# MCU.net
KiCad netlist of a schematic drawn in Altium Designer
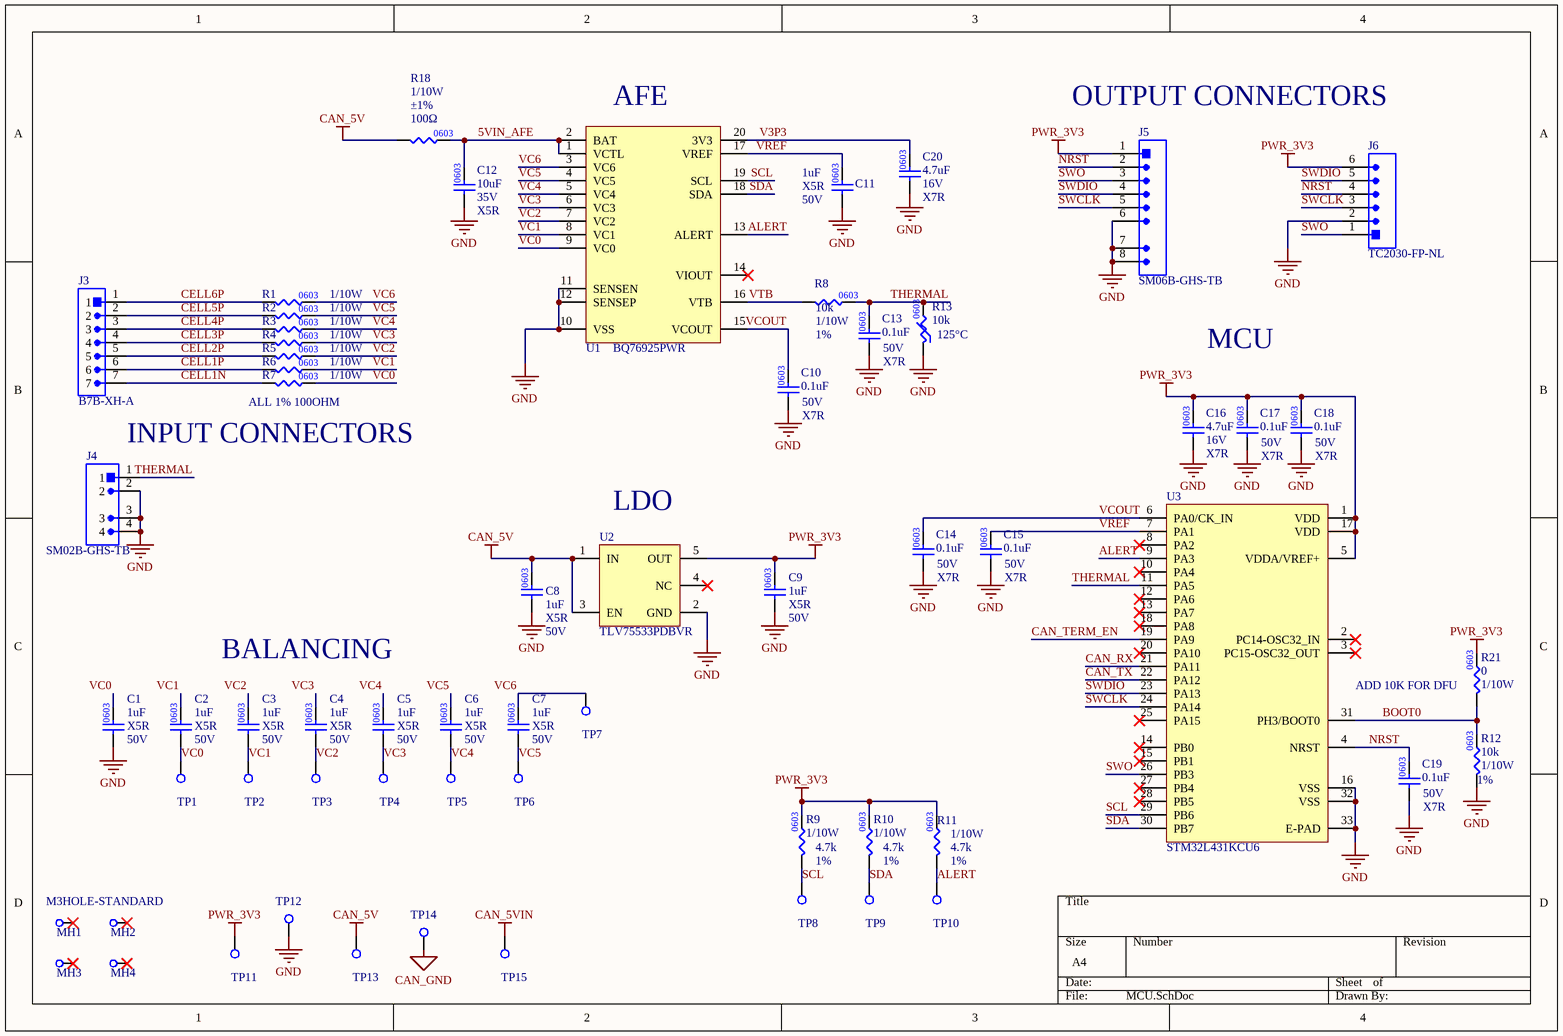
[diagram p0: MCU.SchDoc]

(export (version "E")
  (design (tool "Eeschema 10.0.6"))
  (components
    (comp (ref "C1")
      (value "GRT188R61H105KE13D")
      (footprint ".CAP_0603-Footprint-1")
      (description "CAP CER 1UF 50V X5R 0603")
      (fields
        (field (name "DIELECTRIC") "X5R")
        (field (name "VOLTAGE") "50V")
        (field (name "CAPACITANCE") "1uF")
      )
      (libsource (lib "WARG") (part "CAP"))
    )
    (comp (ref "C2")
      (value "GRT188R61H105KE13D")
      (footprint ".CAP_0603-Footprint-1")
      (description "CAP CER 1UF 50V X5R 0603")
      (fields
        (field (name "DIELECTRIC") "X5R")
        (field (name "VOLTAGE") "50V")
        (field (name "CAPACITANCE") "1uF")
      )
      (libsource (lib "WARG") (part "CAP"))
    )
    (comp (ref "C3")
      (value "GRT188R61H105KE13D")
      (footprint ".CAP_0603-Footprint-1")
      (description "CAP CER 1UF 50V X5R 0603")
      (fields
        (field (name "DIELECTRIC") "X5R")
        (field (name "VOLTAGE") "50V")
        (field (name "CAPACITANCE") "1uF")
      )
      (libsource (lib "WARG") (part "CAP"))
    )
    (comp (ref "C4")
      (value "GRT188R61H105KE13D")
      (footprint ".CAP_0603-Footprint-1")
      (description "CAP CER 1UF 50V X5R 0603")
      (fields
        (field (name "DIELECTRIC") "X5R")
        (field (name "VOLTAGE") "50V")
        (field (name "CAPACITANCE") "1uF")
      )
      (libsource (lib "WARG") (part "CAP"))
    )
    (comp (ref "C5")
      (value "GRT188R61H105KE13D")
      (footprint ".CAP_0603-Footprint-1")
      (description "CAP CER 1UF 50V X5R 0603")
      (fields
        (field (name "DIELECTRIC") "X5R")
        (field (name "VOLTAGE") "50V")
        (field (name "CAPACITANCE") "1uF")
      )
      (libsource (lib "WARG") (part "CAP"))
    )
    (comp (ref "C6")
      (value "GRT188R61H105KE13D")
      (footprint ".CAP_0603-Footprint-1")
      (description "CAP CER 1UF 50V X5R 0603")
      (fields
        (field (name "DIELECTRIC") "X5R")
        (field (name "VOLTAGE") "50V")
        (field (name "CAPACITANCE") "1uF")
      )
      (libsource (lib "WARG") (part "CAP"))
    )
    (comp (ref "C7")
      (value "GRT188R61H105KE13D")
      (footprint ".CAP_0603-Footprint-1")
      (description "CAP CER 1UF 50V X5R 0603")
      (fields
        (field (name "DIELECTRIC") "X5R")
        (field (name "VOLTAGE") "50V")
        (field (name "CAPACITANCE") "1uF")
      )
      (libsource (lib "WARG") (part "CAP"))
    )
    (comp (ref "C8")
      (value "GRT188R61H105KE13D")
      (footprint ".CAP_0603-Footprint-1")
      (description "CAP CER 1UF 50V X5R 0603")
      (fields
        (field (name "DIELECTRIC") "X5R")
        (field (name "VOLTAGE") "50V")
        (field (name "CAPACITANCE") "1uF")
      )
      (libsource (lib "WARG") (part "CAP"))
    )
    (comp (ref "C9")
      (value "GRT188R61H105KE13D")
      (footprint ".CAP_0603-Footprint-1")
      (description "CAP CER 1UF 50V X5R 0603")
      (fields
        (field (name "DIELECTRIC") "X5R")
        (field (name "VOLTAGE") "50V")
        (field (name "CAPACITANCE") "1uF")
      )
      (libsource (lib "WARG") (part "CAP"))
    )
    (comp (ref "C10")
      (value "0.1uF")
      (footprint ".CAP_0603-Footprint-1")
      (description "CAP CER 0.1uF 50V X7R 0603")
      (fields
        (field (name "DIELECTRIC") "X7R")
        (field (name "VOLTAGE") "50V")
        (field (name "TOLERANCE") "10%")
        (field (name "Comment") "GCM188R71H104KA57D")
      )
      (libsource (lib "WARG") (part ".CAP_0603-Symbol-1"))
    )
    (comp (ref "C11")
      (value "GRT188R61H105KE13D")
      (footprint ".CAP_0603-Footprint-1")
      (description "CAP CER 1UF 50V X5R 0603")
      (fields
        (field (name "DIELECTRIC") "X5R")
        (field (name "VOLTAGE") "50V")
        (field (name "CAPACITANCE") "1uF")
      )
      (libsource (lib "WARG") (part "CAP"))
    )
    (comp (ref "C12")
      (value "GRM188R6YA106MA73D")
      (footprint ".CAP_0603-Footprint-1")
      (description "CAP CER 10UF 35V X5R 0603")
      (fields
        (field (name "TOLERANCE") "±20%")
        (field (name "CAPACITANCE") "10uF")
        (field (name "VOLTAGE") "35V")
        (field (name "TEMPERATURE COEFFICIENT") "X5R")
      )
      (libsource (lib "WARG") (part ".CAP_0603-Symbol-1"))
    )
    (comp (ref "C13")
      (value "0.1uF")
      (footprint ".CAP_0603-Footprint-1")
      (description "CAP CER 0.1uF 50V X7R 0603")
      (fields
        (field (name "DIELECTRIC") "X7R")
        (field (name "VOLTAGE") "50V")
        (field (name "TOLERANCE") "10%")
        (field (name "Comment") "GCM188R71H104KA57D")
      )
      (libsource (lib "WARG") (part ".CAP_0603-Symbol-1"))
    )
    (comp (ref "C14")
      (value "0.1uF")
      (footprint ".CAP_0603-Footprint-1")
      (description "CAP CER 0.1uF 50V X7R 0603")
      (fields
        (field (name "DIELECTRIC") "X7R")
        (field (name "VOLTAGE") "50V")
        (field (name "TOLERANCE") "10%")
        (field (name "Comment") "GCM188R71H104KA57D")
      )
      (libsource (lib "WARG") (part ".CAP_0603-Symbol-1"))
    )
    (comp (ref "C15")
      (value "0.1uF")
      (footprint ".CAP_0603-Footprint-1")
      (description "CAP CER 0.1uF 50V X7R 0603")
      (fields
        (field (name "DIELECTRIC") "X7R")
        (field (name "VOLTAGE") "50V")
        (field (name "TOLERANCE") "10%")
        (field (name "Comment") "GCM188R71H104KA57D")
      )
      (libsource (lib "WARG") (part ".CAP_0603-Symbol-1"))
    )
    (comp (ref "C16")
      (value "4.7uF")
      (footprint ".CAP_0603-Footprint-1")
      (description "CAP CER 4.7UF 16V X7R 0603")
      (fields
        (field (name "VOLTAGE RATING") "16V")
        (field (name "TEMPERATURE COEFFICIENT") "X7R")
        (field (name "Comment") "GRM188Z71C475KE21J")
      )
      (libsource (lib "WARG") (part ".CAP_0603-Symbol-1"))
    )
    (comp (ref "C17")
      (value "0.1uF")
      (footprint ".CAP_0603-Footprint-1")
      (description "CAP CER 0.1uF 50V X7R 0603")
      (fields
        (field (name "DIELECTRIC") "X7R")
        (field (name "VOLTAGE") "50V")
        (field (name "TOLERANCE") "10%")
        (field (name "Comment") "GCM188R71H104KA57D")
      )
      (libsource (lib "WARG") (part ".CAP_0603-Symbol-1"))
    )
    (comp (ref "C18")
      (value "0.1uF")
      (footprint ".CAP_0603-Footprint-1")
      (description "CAP CER 0.1uF 50V X7R 0603")
      (fields
        (field (name "DIELECTRIC") "X7R")
        (field (name "VOLTAGE") "50V")
        (field (name "TOLERANCE") "10%")
        (field (name "Comment") "GCM188R71H104KA57D")
      )
      (libsource (lib "WARG") (part ".CAP_0603-Symbol-1"))
    )
    (comp (ref "C19")
      (value "0.1uF")
      (footprint ".CAP_0603-Footprint-1")
      (description "CAP CER 0.1uF 50V X7R 0603")
      (fields
        (field (name "DIELECTRIC") "X7R")
        (field (name "VOLTAGE") "50V")
        (field (name "TOLERANCE") "10%")
        (field (name "Comment") "GCM188R71H104KA57D")
      )
      (libsource (lib "WARG") (part ".CAP_0603-Symbol-1"))
    )
    (comp (ref "C20")
      (value "4.7uF")
      (footprint ".CAP_0603-Footprint-1")
      (description "CAP CER 4.7UF 16V X7R 0603")
      (fields
        (field (name "VOLTAGE RATING") "16V")
        (field (name "TEMPERATURE COEFFICIENT") "X7R")
        (field (name "Comment") "GRM188Z71C475KE21J")
      )
      (libsource (lib "WARG") (part ".CAP_0603-Symbol-1"))
    )
    (comp (ref "J3")
      (value "B7B-XH-A")
      (footprint "JST_B7B-XH-A")
      (description "Connector Header Through Hole 7 position 0.098 (2.50mm)")
      (fields (field (name "MF") "JST Sales"))
      (libsource (lib "WARG") (part "B7B-XH-A"))
    )
    (comp (ref "J4")
      (value "SM02B-GHS-TB")
      (footprint "SM02B-GHS-TB-Footprint-1")
      (description "CONN HEADER SMD R/A 2POS 1.25MM")
      (libsource (lib "WARG") (part "SM02B-GHS-TB-Symbol-1"))
    )
    (comp (ref "J5")
      (value "SM06B-GHS-TB")
      (footprint "SM06B-GHS-TB")
      (description "CONN HEADER SMD R/A 6POS 1.25MM")
      (fields (field (name "VOLTAGE") "50V"))
      (libsource (lib "WARG") (part "SM06B-GHS-TB(LF)(SN)-Symbol-1"))
    )
    (comp (ref "J6")
      (value "TC2030-FP-NL")
      (footprint "TC2030-FP-NL")
      (description "For TC2030-CTX-NL-STDC14 for use with STM32 processors with STLINK-V3 /STLINK-V3MINI")
      (fields (field (name "MANUFACTURER") "Tag-Connect"))
      (libsource (lib "WARG") (part "TC2030-FP-NL"))
    )
    (comp (ref "MH1")
      (value "M3HOLE-STANDARD")
      (footprint "M3HOLE-STANDARD-Footprint-1")
      (description "Standard M3 Mounting hole as defined by mech team, see confluence for reasonning")
      (libsource (lib "WARG") (part "M2HOLE-STANDARD-Symbol-1"))
    )
    (comp (ref "MH2")
      (value "M3HOLE-STANDARD")
      (footprint "M3HOLE-STANDARD-Footprint-1")
      (description "Standard M3 Mounting hole as defined by mech team, see confluence for reasonning")
      (libsource (lib "WARG") (part "M2HOLE-STANDARD-Symbol-1"))
    )
    (comp (ref "MH3")
      (value "M3HOLE-STANDARD")
      (footprint "M3HOLE-STANDARD-Footprint-1")
      (description "Standard M3 Mounting hole as defined by mech team, see confluence for reasonning")
      (libsource (lib "WARG") (part "M2HOLE-STANDARD-Symbol-1"))
    )
    (comp (ref "MH4")
      (value "M3HOLE-STANDARD")
      (footprint "M3HOLE-STANDARD-Footprint-1")
      (description "Standard M3 Mounting hole as defined by mech team, see confluence for reasonning")
      (libsource (lib "WARG") (part "M2HOLE-STANDARD-Symbol-1"))
    )
    (comp (ref "R1")
      (value "RC0603FR-07100RL")
      (footprint ".RES_0603-Footprint-1")
      (description "RES 100 OHM 1% 1/10W 0603")
      (fields (field (name "TOLERANCE") "±1%") (field (name "POWER") "1/10W"))
      (libsource (lib "WARG") (part ".RES_0603-Symbol-1"))
    )
    (comp (ref "R2")
      (value "RC0603FR-07100RL")
      (footprint ".RES_0603-Footprint-1")
      (description "RES 100 OHM 1% 1/10W 0603")
      (fields (field (name "TOLERANCE") "±1%") (field (name "POWER") "1/10W"))
      (libsource (lib "WARG") (part ".RES_0603-Symbol-1"))
    )
    (comp (ref "R3")
      (value "RC0603FR-07100RL")
      (footprint ".RES_0603-Footprint-1")
      (description "RES 100 OHM 1% 1/10W 0603")
      (fields (field (name "TOLERANCE") "±1%") (field (name "POWER") "1/10W"))
      (libsource (lib "WARG") (part ".RES_0603-Symbol-1"))
    )
    (comp (ref "R4")
      (value "RC0603FR-07100RL")
      (footprint ".RES_0603-Footprint-1")
      (description "RES 100 OHM 1% 1/10W 0603")
      (fields (field (name "TOLERANCE") "±1%") (field (name "POWER") "1/10W"))
      (libsource (lib "WARG") (part ".RES_0603-Symbol-1"))
    )
    (comp (ref "R5")
      (value "RC0603FR-07100RL")
      (footprint ".RES_0603-Footprint-1")
      (description "RES 100 OHM 1% 1/10W 0603")
      (fields (field (name "TOLERANCE") "±1%") (field (name "POWER") "1/10W"))
      (libsource (lib "WARG") (part ".RES_0603-Symbol-1"))
    )
    (comp (ref "R6")
      (value "RC0603FR-07100RL")
      (footprint ".RES_0603-Footprint-1")
      (description "RES 100 OHM 1% 1/10W 0603")
      (fields (field (name "TOLERANCE") "±1%") (field (name "POWER") "1/10W"))
      (libsource (lib "WARG") (part ".RES_0603-Symbol-1"))
    )
    (comp (ref "R7")
      (value "RC0603FR-07100RL")
      (footprint ".RES_0603-Footprint-1")
      (description "RES 100 OHM 1% 1/10W 0603")
      (fields (field (name "TOLERANCE") "±1%") (field (name "POWER") "1/10W"))
      (libsource (lib "WARG") (part ".RES_0603-Symbol-1"))
    )
    (comp (ref "R8")
      (value "10k")
      (footprint ".RES_0603-Footprint-1")
      (description "RES 10K OHM 1% 1/10W 0603")
      (fields
        (field (name "TOLERANCE") "1%")
        (field (name "POWER") "1/10W")
        (field (name "Comment") "RC0603FR-0710KL")
      )
      (libsource (lib "WARG") (part ".RES_0603-Symbol-1"))
    )
    (comp (ref "R9")
      (value "RC0603FR-074K7L")
      (footprint ".RES_0603-Footprint-1")
      (description "RES 4.7K OHM 1% 1/10W 0603")
      (fields
        (field (name "TOLERANCE") "1%")
        (field (name "POWER") "1/10W")
        (field (name "RESISTANCE") "4.7k")
      )
      (libsource (lib "WARG") (part ".RES_0603-Symbol-1"))
    )
    (comp (ref "R10")
      (value "RC0603FR-074K7L")
      (footprint ".RES_0603-Footprint-1")
      (description "RES 4.7K OHM 1% 1/10W 0603")
      (fields
        (field (name "TOLERANCE") "1%")
        (field (name "POWER") "1/10W")
        (field (name "RESISTANCE") "4.7k")
      )
      (libsource (lib "WARG") (part ".RES_0603-Symbol-1"))
    )
    (comp (ref "R11")
      (value "RC0603FR-074K7L")
      (footprint ".RES_0603-Footprint-1")
      (description "RES 4.7K OHM 1% 1/10W 0603")
      (fields
        (field (name "TOLERANCE") "1%")
        (field (name "POWER") "1/10W")
        (field (name "RESISTANCE") "4.7k")
      )
      (libsource (lib "WARG") (part ".RES_0603-Symbol-1"))
    )
    (comp (ref "R12")
      (value "10k")
      (footprint ".RES_0603-Footprint-1")
      (description "RES 10K OHM 1% 1/10W 0603")
      (fields
        (field (name "TOLERANCE") "1%")
        (field (name "POWER") "1/10W")
        (field (name "Comment") "RC0603FR-0710KL")
      )
      (libsource (lib "WARG") (part ".RES_0603-Symbol-1"))
    )
    (comp (ref "R13")
      (value "10k")
      (footprint ".RES_0603-Footprint-1")
      (description "THERMISTOR NTC 10KOHM 3380K 0603")
      (fields
        (field (name "TOLERANCE") "1%")
        (field (name "MAX OPERATING TEMPERATURE") "125°C")
        (field (name "Comment") "NTCG163JF103FT1")
      )
      (libsource (lib "WARG") (part ".THERMISTOR_0603-Symbol-1"))
    )
    (comp (ref "R18")
      (value "RC0603FR-07100RL")
      (footprint ".RES_0603-Footprint-1")
      (description "RES 100 OHM 1% 1/10W 0603")
      (fields
        (field (name "RESISTANCE") "100Ω")
        (field (name "TOLERANCE") "±1%")
        (field (name "POWER") "1/10W")
      )
      (libsource (lib "WARG") (part ".RES_0603-Symbol-1"))
    )
    (comp (ref "R21")
      (value "0")
      (footprint ".RES_0603-Footprint-1")
      (description "RES 0 OHM 1% 1/10W 0603")
      (fields
        (field (name "POWER") "1/10W")
        (field (name "TOLERANCE") "1%")
        (field (name "Comment") "RC0603JR-070RL")
      )
      (libsource (lib "WARG") (part ".RES_0603-Symbol-1"))
    )
    (comp (ref "TP1")
      (value "TESTINGPOINT_1MM")
      (footprint "TESTINGPOINT_1MM-Footprint-1")
      (description "Testing Point 1mm Radius")
      (libsource (lib "WARG") (part "TESTINGPOINT_1MM-Symbol-1"))
    )
    (comp (ref "TP2")
      (value "TESTINGPOINT_1MM")
      (footprint "TESTINGPOINT_1MM-Footprint-1")
      (description "Testing Point 1mm Radius")
      (libsource (lib "WARG") (part "TESTINGPOINT_1MM-Symbol-1"))
    )
    (comp (ref "TP3")
      (value "TESTINGPOINT_1MM")
      (footprint "TESTINGPOINT_1MM-Footprint-1")
      (description "Testing Point 1mm Radius")
      (libsource (lib "WARG") (part "TESTINGPOINT_1MM-Symbol-1"))
    )
    (comp (ref "TP4")
      (value "TESTINGPOINT_1MM")
      (footprint "TESTINGPOINT_1MM-Footprint-1")
      (description "Testing Point 1mm Radius")
      (libsource (lib "WARG") (part "TESTINGPOINT_1MM-Symbol-1"))
    )
    (comp (ref "TP5")
      (value "TESTINGPOINT_1MM")
      (footprint "TESTINGPOINT_1MM-Footprint-1")
      (description "Testing Point 1mm Radius")
      (libsource (lib "WARG") (part "TESTINGPOINT_1MM-Symbol-1"))
    )
    (comp (ref "TP6")
      (value "TESTINGPOINT_1MM")
      (footprint "TESTINGPOINT_1MM-Footprint-1")
      (description "Testing Point 1mm Radius")
      (libsource (lib "WARG") (part "TESTINGPOINT_1MM-Symbol-1"))
    )
    (comp (ref "TP7")
      (value "TESTINGPOINT_1MM")
      (footprint "TESTINGPOINT_1MM-Footprint-1")
      (description "Testing Point 1mm Radius")
      (libsource (lib "WARG") (part "TESTINGPOINT_1MM-Symbol-1"))
    )
    (comp (ref "TP8")
      (value "TESTINGPOINT_1MM")
      (footprint "TESTINGPOINT_1MM-Footprint-1")
      (description "Testing Point 1mm Radius")
      (libsource (lib "WARG") (part "TESTINGPOINT_1MM-Symbol-1"))
    )
    (comp (ref "TP9")
      (value "TESTINGPOINT_1MM")
      (footprint "TESTINGPOINT_1MM-Footprint-1")
      (description "Testing Point 1mm Radius")
      (libsource (lib "WARG") (part "TESTINGPOINT_1MM-Symbol-1"))
    )
    (comp (ref "TP10")
      (value "TESTINGPOINT_1MM")
      (footprint "TESTINGPOINT_1MM-Footprint-1")
      (description "Testing Point 1mm Radius")
      (libsource (lib "WARG") (part "TESTINGPOINT_1MM-Symbol-1"))
    )
    (comp (ref "TP11")
      (value "TESTINGPOINT_1MM")
      (footprint "TESTINGPOINT_1MM-Footprint-1")
      (description "Testing Point 1mm Radius")
      (libsource (lib "WARG") (part "TESTINGPOINT_1MM-Symbol-1"))
    )
    (comp (ref "TP12")
      (value "TESTINGPOINT_1MM")
      (footprint "TESTINGPOINT_1MM-Footprint-1")
      (description "Testing Point 1mm Radius")
      (libsource (lib "WARG") (part "TESTINGPOINT_1MM-Symbol-1"))
    )
    (comp (ref "TP13")
      (value "TESTINGPOINT_1MM")
      (footprint "TESTINGPOINT_1MM-Footprint-1")
      (description "Testing Point 1mm Radius")
      (libsource (lib "WARG") (part "TESTINGPOINT_1MM-Symbol-1"))
    )
    (comp (ref "TP14")
      (value "TESTINGPOINT_1MM")
      (footprint "TESTINGPOINT_1MM-Footprint-1")
      (description "Testing Point 1mm Radius")
      (libsource (lib "WARG") (part "TESTINGPOINT_1MM-Symbol-1"))
    )
    (comp (ref "TP15")
      (value "TESTINGPOINT_1MM")
      (footprint "TESTINGPOINT_1MM-Footprint-1")
      (description "Testing Point 1mm Radius")
      (libsource (lib "WARG") (part "TESTINGPOINT_1MM-Symbol-1"))
    )
    (comp (ref "U1")
      (value "BQ76925PWR")
      (footprint "BQ76925PWR-Footprint-1")
      (description "Power Supply Support Circuit, Adjustable, 1 Channel, PDSO20")
      (libsource (lib "WARG") (part "BQ76925PWR"))
    )
    (comp (ref "U2")
      (value "TLV75533PDBVR")
      (footprint "SOT-23-5")
      (description "IC REG LINEAR 3.3V 500MA SOT23-5")
      (libsource (lib "WARG") (part "TLV75533PDBVR-Symbol-1"))
    )
    (comp (ref "U3")
      (value "STM32L431KCU6")
      (footprint "STM32L431KCU6-Footprint-1")
      (description "IC MCU 32BIT 256KB FLSH 32UFQFPN")
      (libsource (lib "WARG") (part "STM32L431KCU6-Symbol-1"))
    )
  )
  (nets
    (net (code "1") (name "/5VIN_AFE") (class "Default")
      (node (ref "C12") (pin "2") (pinfunction "2_2") (pintype "passive"))
      (node (ref "R18") (pin "2") (pinfunction "2_2") (pintype "passive"))
      (node (ref "U1") (pin "1") (pinfunction "VCTL_1") (pintype "passive"))
      (node (ref "U1") (pin "2") (pinfunction "BAT_2") (pintype "passive"))
    )
    (net (code "2") (name "/ALERT") (class "Default")
      (node (ref "R11") (pin "1") (pinfunction "1_1") (pintype "passive"))
      (node (ref "TP10") (pin "1") (pinfunction "1_1") (pintype "passive"))
      (node (ref "U1") (pin "13") (pinfunction "ALERT_13") (pintype "passive"))
      (node (ref "U3") (pin "9") (pinfunction "PA3_9") (pintype "passive"))
    )
    (net (code "3") (name "/BOOT0") (class "Default")
      (node (ref "R12") (pin "2") (pinfunction "2_2") (pintype "passive"))
      (node (ref "R21") (pin "1") (pinfunction "1_1") (pintype "passive"))
      (node (ref "U3") (pin "31") (pinfunction "PH3/BOOT0_31") (pintype "passive"))
    )
    (net (code "4") (name "/CAN_RX") (class "Default")
      (node (ref "U3") (pin "21") (pinfunction "PA11_21") (pintype "passive"))
    )
    (net (code "5") (name "/CAN_TERM_EN") (class "Default")
      (node (ref "U3") (pin "19") (pinfunction "PA9_19") (pintype "passive"))
    )
    (net (code "6") (name "/CAN_TX") (class "Default")
      (node (ref "U3") (pin "22") (pinfunction "PA12_22") (pintype "passive"))
    )
    (net (code "7") (name "/CELL1N") (class "Default")
      (node (ref "J3") (pin "7") (pinfunction "7_7") (pintype "passive"))
      (node (ref "R7") (pin "1") (pinfunction "1_1") (pintype "passive"))
    )
    (net (code "8") (name "/CELL1P") (class "Default")
      (node (ref "J3") (pin "6") (pinfunction "6_6") (pintype "passive"))
      (node (ref "R6") (pin "1") (pinfunction "1_1") (pintype "passive"))
    )
    (net (code "9") (name "/CELL2P") (class "Default")
      (node (ref "J3") (pin "5") (pinfunction "5_5") (pintype "passive"))
      (node (ref "R5") (pin "1") (pinfunction "1_1") (pintype "passive"))
    )
    (net (code "10") (name "/CELL3P") (class "Default")
      (node (ref "J3") (pin "4") (pinfunction "4_4") (pintype "passive"))
      (node (ref "R4") (pin "1") (pinfunction "1_1") (pintype "passive"))
    )
    (net (code "11") (name "/CELL4P") (class "Default")
      (node (ref "J3") (pin "3") (pinfunction "3_3") (pintype "passive"))
      (node (ref "R3") (pin "1") (pinfunction "1_1") (pintype "passive"))
    )
    (net (code "12") (name "/CELL5P") (class "Default")
      (node (ref "J3") (pin "2") (pinfunction "2_2") (pintype "passive"))
      (node (ref "R2") (pin "1") (pinfunction "1_1") (pintype "passive"))
    )
    (net (code "13") (name "/CELL6P") (class "Default")
      (node (ref "J3") (pin "1") (pinfunction "1_1") (pintype "passive"))
      (node (ref "R1") (pin "1") (pinfunction "1_1") (pintype "passive"))
    )
    (net (code "14") (name "/NRST") (class "Default")
      (node (ref "C19") (pin "2") (pinfunction "2_2") (pintype "passive"))
      (node (ref "J5") (pin "2") (pinfunction "2_2") (pintype "passive"))
      (node (ref "J6") (pin "4") (pinfunction "4_4") (pintype "passive"))
      (node (ref "U3") (pin "4") (pinfunction "NRST_4") (pintype "passive"))
    )
    (net (code "15") (name "/SCL") (class "Default")
      (node (ref "R9") (pin "1") (pinfunction "1_1") (pintype "passive"))
      (node (ref "TP8") (pin "1") (pinfunction "1_1") (pintype "passive"))
      (node (ref "U1") (pin "19") (pinfunction "SCL_19") (pintype "passive"))
      (node (ref "U3") (pin "29") (pinfunction "PB6_29") (pintype "passive"))
    )
    (net (code "16") (name "/SDA") (class "Default")
      (node (ref "R10") (pin "1") (pinfunction "1_1") (pintype "passive"))
      (node (ref "TP9") (pin "1") (pinfunction "1_1") (pintype "passive"))
      (node (ref "U1") (pin "18") (pinfunction "SDA_18") (pintype "passive"))
      (node (ref "U3") (pin "30") (pinfunction "PB7_30") (pintype "passive"))
    )
    (net (code "17") (name "/SWCLK") (class "Default")
      (node (ref "J5") (pin "5") (pinfunction "5_5") (pintype "passive"))
      (node (ref "J6") (pin "3") (pinfunction "3_3") (pintype "passive"))
      (node (ref "U3") (pin "24") (pinfunction "PA14_24") (pintype "passive"))
    )
    (net (code "18") (name "/SWDIO") (class "Default")
      (node (ref "J5") (pin "4") (pinfunction "4_4") (pintype "passive"))
      (node (ref "J6") (pin "5") (pinfunction "5_5") (pintype "passive"))
      (node (ref "U3") (pin "23") (pinfunction "PA13_23") (pintype "passive"))
    )
    (net (code "19") (name "/SWO") (class "Default")
      (node (ref "J5") (pin "3") (pinfunction "3_3") (pintype "passive"))
      (node (ref "J6") (pin "1") (pinfunction "1_1") (pintype "passive"))
      (node (ref "U3") (pin "26") (pinfunction "PB3_26") (pintype "passive"))
    )
    (net (code "20") (name "/THERMAL") (class "Default")
      (node (ref "C13") (pin "2") (pinfunction "2_2") (pintype "passive"))
      (node (ref "J4") (pin "1") (pinfunction "1_1") (pintype "passive"))
      (node (ref "R13") (pin "2") (pinfunction "2_2") (pintype "passive"))
      (node (ref "R8") (pin "2") (pinfunction "2_2") (pintype "passive"))
      (node (ref "U3") (pin "11") (pinfunction "PA5_11") (pintype "passive"))
    )
    (net (code "21") (name "/V3P3") (class "Default")
      (node (ref "C20") (pin "2") (pinfunction "2_2") (pintype "passive"))
      (node (ref "U1") (pin "20") (pinfunction "3V3_20") (pintype "passive"))
    )
    (net (code "22") (name "/VC0") (class "Default")
      (node (ref "C1") (pin "2") (pinfunction "2_2") (pintype "passive"))
      (node (ref "C2") (pin "1") (pinfunction "1_1") (pintype "passive"))
      (node (ref "R7") (pin "2") (pinfunction "2_2") (pintype "passive"))
      (node (ref "TP1") (pin "1") (pinfunction "1_1") (pintype "passive"))
      (node (ref "U1") (pin "9") (pinfunction "VC0_9") (pintype "passive"))
    )
    (net (code "23") (name "/VC1") (class "Default")
      (node (ref "C2") (pin "2") (pinfunction "2_2") (pintype "passive"))
      (node (ref "C3") (pin "1") (pinfunction "1_1") (pintype "passive"))
      (node (ref "R6") (pin "2") (pinfunction "2_2") (pintype "passive"))
      (node (ref "TP2") (pin "1") (pinfunction "1_1") (pintype "passive"))
      (node (ref "U1") (pin "8") (pinfunction "VC1_8") (pintype "passive"))
    )
    (net (code "24") (name "/VC2") (class "Default")
      (node (ref "C3") (pin "2") (pinfunction "2_2") (pintype "passive"))
      (node (ref "C4") (pin "1") (pinfunction "1_1") (pintype "passive"))
      (node (ref "R5") (pin "2") (pinfunction "2_2") (pintype "passive"))
      (node (ref "TP3") (pin "1") (pinfunction "1_1") (pintype "passive"))
      (node (ref "U1") (pin "7") (pinfunction "VC2_7") (pintype "passive"))
    )
    (net (code "25") (name "/VC3") (class "Default")
      (node (ref "C4") (pin "2") (pinfunction "2_2") (pintype "passive"))
      (node (ref "C5") (pin "1") (pinfunction "1_1") (pintype "passive"))
      (node (ref "R4") (pin "2") (pinfunction "2_2") (pintype "passive"))
      (node (ref "TP4") (pin "1") (pinfunction "1_1") (pintype "passive"))
      (node (ref "U1") (pin "6") (pinfunction "VC3_6") (pintype "passive"))
    )
    (net (code "26") (name "/VC4") (class "Default")
      (node (ref "C5") (pin "2") (pinfunction "2_2") (pintype "passive"))
      (node (ref "C6") (pin "1") (pinfunction "1_1") (pintype "passive"))
      (node (ref "R3") (pin "2") (pinfunction "2_2") (pintype "passive"))
      (node (ref "TP5") (pin "1") (pinfunction "1_1") (pintype "passive"))
      (node (ref "U1") (pin "5") (pinfunction "VC4_5") (pintype "passive"))
    )
    (net (code "27") (name "/VC5") (class "Default")
      (node (ref "C6") (pin "2") (pinfunction "2_2") (pintype "passive"))
      (node (ref "C7") (pin "1") (pinfunction "1_1") (pintype "passive"))
      (node (ref "R2") (pin "2") (pinfunction "2_2") (pintype "passive"))
      (node (ref "TP6") (pin "1") (pinfunction "1_1") (pintype "passive"))
      (node (ref "U1") (pin "4") (pinfunction "VC5_4") (pintype "passive"))
    )
    (net (code "28") (name "/VC6") (class "Default")
      (node (ref "C7") (pin "2") (pinfunction "2_2") (pintype "passive"))
      (node (ref "R1") (pin "2") (pinfunction "2_2") (pintype "passive"))
      (node (ref "TP7") (pin "1") (pinfunction "1_1") (pintype "passive"))
      (node (ref "U1") (pin "3") (pinfunction "VC6_3") (pintype "passive"))
    )
    (net (code "29") (name "/VCOUT") (class "Default")
      (node (ref "C10") (pin "2") (pinfunction "2_2") (pintype "passive"))
      (node (ref "C14") (pin "2") (pinfunction "2_2") (pintype "passive"))
      (node (ref "U1") (pin "15") (pinfunction "VCOUT_15") (pintype "passive"))
      (node (ref "U3") (pin "6") (pinfunction "PA0/CK_IN_6") (pintype "passive"))
    )
    (net (code "30") (name "/VREF") (class "Default")
      (node (ref "C11") (pin "2") (pinfunction "2_2") (pintype "passive"))
      (node (ref "C15") (pin "2") (pinfunction "2_2") (pintype "passive"))
      (node (ref "U1") (pin "17") (pinfunction "VREF_17") (pintype "passive"))
      (node (ref "U3") (pin "7") (pinfunction "PA1_7") (pintype "passive"))
    )
    (net (code "31") (name "/VTB") (class "Default")
      (node (ref "R8") (pin "1") (pinfunction "1_1") (pintype "passive"))
      (node (ref "U1") (pin "16") (pinfunction "VTB_16") (pintype "passive"))
    )
    (net (code "32") (name "CAN_5V") (class "Default")
      (node (ref "C8") (pin "2") (pinfunction "2_2") (pintype "passive"))
      (node (ref "R18") (pin "1") (pinfunction "1_1") (pintype "passive"))
      (node (ref "TP13") (pin "1") (pinfunction "1_1") (pintype "passive"))
      (node (ref "U2") (pin "1") (pinfunction "IN_1") (pintype "passive"))
      (node (ref "U2") (pin "3") (pinfunction "EN_3") (pintype "passive"))
    )
    (net (code "33") (name "CAN_5VIN") (class "Default")
      (node (ref "TP15") (pin "1") (pinfunction "1_1") (pintype "passive"))
    )
    (net (code "34") (name "CAN_GND") (class "Default")
      (node (ref "TP14") (pin "1") (pinfunction "1_1") (pintype "passive"))
    )
    (net (code "35") (name "GND") (class "Default")
      (node (ref "C1") (pin "1") (pinfunction "1_1") (pintype "passive"))
      (node (ref "C10") (pin "1") (pinfunction "1_1") (pintype "passive"))
      (node (ref "C11") (pin "1") (pinfunction "1_1") (pintype "passive"))
      (node (ref "C12") (pin "1") (pinfunction "1_1") (pintype "passive"))
      (node (ref "C13") (pin "1") (pinfunction "1_1") (pintype "passive"))
      (node (ref "C14") (pin "1") (pinfunction "1_1") (pintype "passive"))
      (node (ref "C15") (pin "1") (pinfunction "1_1") (pintype "passive"))
      (node (ref "C16") (pin "1") (pinfunction "1_1") (pintype "passive"))
      (node (ref "C17") (pin "1") (pinfunction "1_1") (pintype "passive"))
      (node (ref "C18") (pin "1") (pinfunction "1_1") (pintype "passive"))
      (node (ref "C19") (pin "1") (pinfunction "1_1") (pintype "passive"))
      (node (ref "C20") (pin "1") (pinfunction "1_1") (pintype "passive"))
      (node (ref "C8") (pin "1") (pinfunction "1_1") (pintype "passive"))
      (node (ref "C9") (pin "1") (pinfunction "1_1") (pintype "passive"))
      (node (ref "J4") (pin "2") (pinfunction "2_2") (pintype "passive"))
      (node (ref "J4") (pin "3") (pinfunction "3_3") (pintype "passive"))
      (node (ref "J4") (pin "4") (pinfunction "4_4") (pintype "passive"))
      (node (ref "J5") (pin "6") (pinfunction "6_6") (pintype "passive"))
      (node (ref "J5") (pin "7") (pinfunction "7_7") (pintype "passive"))
      (node (ref "J5") (pin "8") (pinfunction "8_8") (pintype "passive"))
      (node (ref "J6") (pin "2") (pinfunction "2_2") (pintype "passive"))
      (node (ref "R12") (pin "1") (pinfunction "1_1") (pintype "passive"))
      (node (ref "R13") (pin "1") (pinfunction "1_1") (pintype "passive"))
      (node (ref "TP12") (pin "1") (pinfunction "1_1") (pintype "passive"))
      (node (ref "U1") (pin "10") (pinfunction "VSS_10") (pintype "passive"))
      (node (ref "U1") (pin "11") (pinfunction "SENSEN_11") (pintype "passive"))
      (node (ref "U1") (pin "12") (pinfunction "SENSEP_12") (pintype "passive"))
      (node (ref "U2") (pin "2") (pinfunction "GND_2") (pintype "passive"))
      (node (ref "U3") (pin "16") (pinfunction "VSS_16") (pintype "passive"))
      (node (ref "U3") (pin "32") (pinfunction "VSS_32") (pintype "passive"))
      (node (ref "U3") (pin "33") (pinfunction "E-PAD_33") (pintype "passive"))
    )
    (net (code "36") (name "PWR_3V3") (class "Default")
      (node (ref "C16") (pin "2") (pinfunction "2_2") (pintype "passive"))
      (node (ref "C17") (pin "2") (pinfunction "2_2") (pintype "passive"))
      (node (ref "C18") (pin "2") (pinfunction "2_2") (pintype "passive"))
      (node (ref "C9") (pin "2") (pinfunction "2_2") (pintype "passive"))
      (node (ref "J5") (pin "1") (pinfunction "1_1") (pintype "passive"))
      (node (ref "J6") (pin "6") (pinfunction "6_6") (pintype "passive"))
      (node (ref "R10") (pin "2") (pinfunction "2_2") (pintype "passive"))
      (node (ref "R11") (pin "2") (pinfunction "2_2") (pintype "passive"))
      (node (ref "R21") (pin "2") (pinfunction "2_2") (pintype "passive"))
      (node (ref "R9") (pin "2") (pinfunction "2_2") (pintype "passive"))
      (node (ref "TP11") (pin "1") (pinfunction "1_1") (pintype "passive"))
      (node (ref "U2") (pin "5") (pinfunction "OUT_5") (pintype "passive"))
      (node (ref "U3") (pin "1") (pinfunction "VDD_1") (pintype "passive"))
      (node (ref "U3") (pin "17") (pinfunction "VDD_17") (pintype "passive"))
      (node (ref "U3") (pin "5") (pinfunction "VDDA/VREF+_5") (pintype "passive"))
    )
    (net (code "37") (name "unconnected-(MH1-Pad1)") (class "Default")
      (node (ref "MH1") (pin "1") (pinfunction "1_1") (pintype "passive+no_connect"))
    )
    (net (code "38") (name "unconnected-(MH2-Pad1)") (class "Default")
      (node (ref "MH2") (pin "1") (pinfunction "1_1") (pintype "passive+no_connect"))
    )
    (net (code "39") (name "unconnected-(MH3-Pad1)") (class "Default")
      (node (ref "MH3") (pin "1") (pinfunction "1_1") (pintype "passive+no_connect"))
    )
    (net (code "40") (name "unconnected-(MH4-Pad1)") (class "Default")
      (node (ref "MH4") (pin "1") (pinfunction "1_1") (pintype "passive+no_connect"))
    )
    (net (code "41") (name "unconnected-(U1-VIOUT-Pad14)") (class "Default")
      (node (ref "U1") (pin "14") (pinfunction "VIOUT_14") (pintype "passive+no_connect"))
    )
    (net (code "42") (name "unconnected-(U2-NC-Pad4)") (class "Default")
      (node (ref "U2") (pin "4") (pinfunction "NC_4") (pintype "passive+no_connect"))
    )
    (net (code "43") (name "unconnected-(U3-PA2-Pad8)") (class "Default")
      (node (ref "U3") (pin "8") (pinfunction "PA2_8") (pintype "passive+no_connect"))
    )
    (net (code "44") (name "unconnected-(U3-PA4-Pad10)") (class "Default")
      (node (ref "U3") (pin "10") (pinfunction "PA4_10") (pintype "passive+no_connect"))
    )
    (net (code "45") (name "unconnected-(U3-PA6-Pad12)") (class "Default")
      (node (ref "U3") (pin "12") (pinfunction "PA6_12") (pintype "passive+no_connect"))
    )
    (net (code "46") (name "unconnected-(U3-PA7-Pad13)") (class "Default")
      (node (ref "U3") (pin "13") (pinfunction "PA7_13") (pintype "passive+no_connect"))
    )
    (net (code "47") (name "unconnected-(U3-PA8-Pad18)") (class "Default")
      (node (ref "U3") (pin "18") (pinfunction "PA8_18") (pintype "passive+no_connect"))
    )
    (net (code "48") (name "unconnected-(U3-PA10-Pad20)") (class "Default")
      (node (ref "U3") (pin "20") (pinfunction "PA10_20") (pintype "passive+no_connect"))
    )
    (net (code "49") (name "unconnected-(U3-PA15-Pad25)") (class "Default")
      (node (ref "U3") (pin "25") (pinfunction "PA15_25") (pintype "passive+no_connect"))
    )
    (net (code "50") (name "unconnected-(U3-PB0-Pad14)") (class "Default")
      (node (ref "U3") (pin "14") (pinfunction "PB0_14") (pintype "passive+no_connect"))
    )
    (net (code "51") (name "unconnected-(U3-PB1-Pad15)") (class "Default")
      (node (ref "U3") (pin "15") (pinfunction "PB1_15") (pintype "passive+no_connect"))
    )
    (net (code "52") (name "unconnected-(U3-PB4-Pad27)") (class "Default")
      (node (ref "U3") (pin "27") (pinfunction "PB4_27") (pintype "passive+no_connect"))
    )
    (net (code "53") (name "unconnected-(U3-PB5-Pad28)") (class "Default")
      (node (ref "U3") (pin "28") (pinfunction "PB5_28") (pintype "passive+no_connect"))
    )
    (net (code "54") (name "unconnected-(U3-PC14-OSC32_IN-Pad2)") (class "Default")
      (node (ref "U3") (pin "2") (pinfunction "PC14-OSC32_IN_2") (pintype "passive+no_connect"))
    )
    (net (code "55") (name "unconnected-(U3-PC15-OSC32_OUT-Pad3)") (class "Default")
      (node (ref "U3") (pin "3") (pinfunction "PC15-OSC32_OUT_3") (pintype "passive+no_connect"))
    )
  )
)
